# gate_driver2.net
KiCad netlist of a schematic drawn in EAGLE
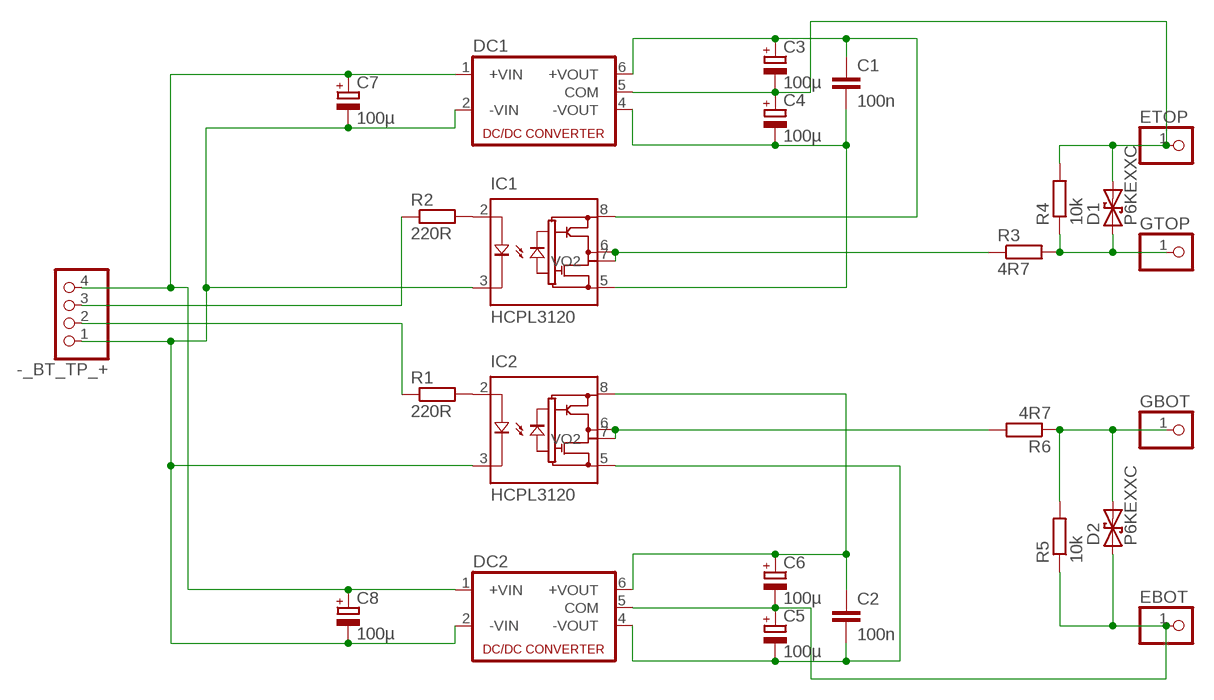
[diagram p0: schematic, sheet 1]

(export (version "E")
  (design (tool "Eeschema 10.0.6"))
  (components
    (comp (ref "-_BT_TP_+")
      (value "PINHD-1X4")
      (footprint "eagle-import:1X04")
      (libsource (lib "eagle-import") (part "PINHD-1X4"))
    )
    (comp (ref "C1")
      (value "100n")
      (footprint "eagle-import:C050-025X075")
      (libsource (lib "eagle-import") (part "C-EU050-025X075"))
    )
    (comp (ref "C2")
      (value "100n")
      (footprint "eagle-import:C050-025X075")
      (libsource (lib "eagle-import") (part "C-EU050-025X075"))
    )
    (comp (ref "C3")
      (value "100µ")
      (footprint "eagle-import:E2,5-6E")
      (libsource (lib "eagle-import") (part "CPOL-EUE2,5-6E"))
    )
    (comp (ref "C4")
      (value "100µ")
      (footprint "eagle-import:E2,5-6E")
      (libsource (lib "eagle-import") (part "CPOL-EUE2,5-6E"))
    )
    (comp (ref "C5")
      (value "100µ")
      (footprint "eagle-import:E2,5-6E")
      (libsource (lib "eagle-import") (part "CPOL-EUE2,5-6E"))
    )
    (comp (ref "C6")
      (value "100µ")
      (footprint "eagle-import:E2,5-6E")
      (libsource (lib "eagle-import") (part "CPOL-EUE2,5-6E"))
    )
    (comp (ref "C7")
      (value "100µ")
      (footprint "eagle-import:E2,5-5")
      (libsource (lib "eagle-import") (part "CPOL-EUE2.5-5"))
    )
    (comp (ref "C8")
      (value "100µ")
      (footprint "eagle-import:E2,5-5")
      (libsource (lib "eagle-import") (part "CPOL-EUE2.5-5"))
    )
    (comp (ref "D1")
      (value "P6KEXXC")
      (footprint "eagle-import:CB417-15")
      (libsource (lib "eagle-import") (part "P6KEXXC"))
    )
    (comp (ref "D2")
      (value "P6KEXXC")
      (footprint "eagle-import:CB417-15")
      (libsource (lib "eagle-import") (part "P6KEXXC"))
    )
    (comp (ref "DC1")
      (value "NMA")
      (footprint "eagle-import:NMA")
      (libsource (lib "eagle-import") (part "NMA"))
    )
    (comp (ref "DC2")
      (value "NMA")
      (footprint "eagle-import:NMA")
      (libsource (lib "eagle-import") (part "NMA"))
    )
    (comp (ref "EBOT")
      (value "PINHD-1X1")
      (footprint "eagle-import:1X01")
      (libsource (lib "eagle-import") (part "PINHD-1X1"))
    )
    (comp (ref "ETOP")
      (value "PINHD-1X1")
      (footprint "eagle-import:1X01")
      (libsource (lib "eagle-import") (part "PINHD-1X1"))
    )
    (comp (ref "GBOT")
      (value "PINHD-1X1")
      (footprint "eagle-import:1X01")
      (libsource (lib "eagle-import") (part "PINHD-1X1"))
    )
    (comp (ref "GTOP")
      (value "PINHD-1X1")
      (footprint "eagle-import:1X01")
      (libsource (lib "eagle-import") (part "PINHD-1X1"))
    )
    (comp (ref "IC1")
      (value "HCPL3120")
      (footprint "eagle-import:DIL08")
      (libsource (lib "eagle-import") (part "HCPL3120"))
    )
    (comp (ref "IC2")
      (value "HCPL3120")
      (footprint "eagle-import:DIL08")
      (libsource (lib "eagle-import") (part "HCPL3120"))
    )
    (comp (ref "R1")
      (value "220R")
      (footprint "eagle-import:0207_10")
      (libsource (lib "eagle-import") (part "R-EU_0207/10"))
    )
    (comp (ref "R2")
      (value "220R")
      (footprint "eagle-import:0207_10")
      (libsource (lib "eagle-import") (part "R-EU_0207/10"))
    )
    (comp (ref "R3")
      (value "4R7")
      (footprint "eagle-import:0309_12")
      (libsource (lib "eagle-import") (part "R-EU_0309/12"))
    )
    (comp (ref "R4")
      (value "10k")
      (footprint "eagle-import:0207_10")
      (libsource (lib "eagle-import") (part "R-EU_0207/10"))
    )
    (comp (ref "R5")
      (value "10k")
      (footprint "eagle-import:0207_10")
      (libsource (lib "eagle-import") (part "R-EU_0207/10"))
    )
    (comp (ref "R6")
      (value "4R7")
      (footprint "eagle-import:0309_12")
      (libsource (lib "eagle-import") (part "R-EU_0309/12"))
    )
  )
  (nets
    (net (code "1") (name "Net-(-_BT_TP_+-Pad2)") (class "Default")
      (node (ref "-_BT_TP_+") (pin "2") (pinfunction "2_2") (pintype "passive"))
      (node (ref "R1") (pin "1") (pinfunction "1_1") (pintype "passive"))
    )
    (net (code "2") (name "Net-(-_BT_TP_+-Pad3)") (class "Default")
      (node (ref "-_BT_TP_+") (pin "3") (pinfunction "3_3") (pintype "passive"))
      (node (ref "R2") (pin "1") (pinfunction "1_1") (pintype "passive"))
    )
    (net (code "3") (name "Net-(D1-1)") (class "Default")
      (node (ref "D1") (pin "A") (pinfunction "1_A") (pintype "passive"))
      (node (ref "GTOP") (pin "1") (pinfunction "1_1") (pintype "passive"))
      (node (ref "R3") (pin "2") (pinfunction "2_2") (pintype "passive"))
      (node (ref "R4") (pin "1") (pinfunction "1_1") (pintype "passive"))
    )
    (net (code "4") (name "Net-(D1-2)") (class "Default")
      (node (ref "C3") (pin "-") (pinfunction "-_-") (pintype "passive"))
      (node (ref "C4") (pin "+") (pinfunction "+_+") (pintype "passive"))
      (node (ref "D1") (pin "C") (pinfunction "2_C") (pintype "passive"))
      (node (ref "DC1") (pin "5") (pinfunction "COM_5") (pintype "passive"))
      (node (ref "ETOP") (pin "1") (pinfunction "1_1") (pintype "passive"))
      (node (ref "R4") (pin "2") (pinfunction "2_2") (pintype "passive"))
    )
    (net (code "5") (name "Net-(D2-1)") (class "Default")
      (node (ref "C5") (pin "+") (pinfunction "+_+") (pintype "passive"))
      (node (ref "C6") (pin "-") (pinfunction "-_-") (pintype "passive"))
      (node (ref "D2") (pin "A") (pinfunction "1_A") (pintype "passive"))
      (node (ref "DC2") (pin "5") (pinfunction "COM_5") (pintype "passive"))
      (node (ref "EBOT") (pin "1") (pinfunction "1_1") (pintype "passive"))
      (node (ref "R5") (pin "1") (pinfunction "1_1") (pintype "passive"))
    )
    (net (code "6") (name "Net-(D2-2)") (class "Default")
      (node (ref "D2") (pin "C") (pinfunction "2_C") (pintype "passive"))
      (node (ref "GBOT") (pin "1") (pinfunction "1_1") (pintype "passive"))
      (node (ref "R5") (pin "2") (pinfunction "2_2") (pintype "passive"))
      (node (ref "R6") (pin "1") (pinfunction "1_1") (pintype "passive"))
    )
    (net (code "7") (name "Net-(DC1-+VIN)") (class "Default")
      (node (ref "-_BT_TP_+") (pin "4") (pinfunction "4_4") (pintype "passive"))
      (node (ref "C7") (pin "+") (pinfunction "+_+") (pintype "passive"))
      (node (ref "C8") (pin "+") (pinfunction "+_+") (pintype "passive"))
      (node (ref "DC1") (pin "1") (pinfunction "+VIN_1") (pintype "passive"))
      (node (ref "DC2") (pin "1") (pinfunction "+VIN_1") (pintype "passive"))
    )
    (net (code "8") (name "Net-(DC1-+VOUT)") (class "Default")
      (node (ref "C1") (pin "1") (pinfunction "1_1") (pintype "passive"))
      (node (ref "C3") (pin "+") (pinfunction "+_+") (pintype "passive"))
      (node (ref "DC1") (pin "6") (pinfunction "+VOUT_6") (pintype "passive"))
      (node (ref "IC1") (pin "8") (pinfunction "VCC_8") (pintype "passive"))
    )
    (net (code "9") (name "Net-(DC1--VIN)") (class "Default")
      (node (ref "-_BT_TP_+") (pin "1") (pinfunction "1_1") (pintype "passive"))
      (node (ref "C7") (pin "-") (pinfunction "-_-") (pintype "passive"))
      (node (ref "C8") (pin "-") (pinfunction "-_-") (pintype "passive"))
      (node (ref "DC1") (pin "2") (pinfunction "-VIN_2") (pintype "passive"))
      (node (ref "DC2") (pin "2") (pinfunction "-VIN_2") (pintype "passive"))
      (node (ref "IC1") (pin "3") (pinfunction "CATHODE_3") (pintype "passive"))
      (node (ref "IC2") (pin "3") (pinfunction "CATHODE_3") (pintype "passive"))
    )
    (net (code "10") (name "Net-(DC1--VOUT)") (class "Default")
      (node (ref "C1") (pin "2") (pinfunction "2_2") (pintype "passive"))
      (node (ref "C4") (pin "-") (pinfunction "-_-") (pintype "passive"))
      (node (ref "DC1") (pin "4") (pinfunction "-VOUT_4") (pintype "passive"))
      (node (ref "IC1") (pin "5") (pinfunction "VEE_5") (pintype "passive"))
    )
    (net (code "11") (name "Net-(DC2-+VOUT)") (class "Default")
      (node (ref "C2") (pin "1") (pinfunction "1_1") (pintype "passive"))
      (node (ref "C6") (pin "+") (pinfunction "+_+") (pintype "passive"))
      (node (ref "DC2") (pin "6") (pinfunction "+VOUT_6") (pintype "passive"))
      (node (ref "IC2") (pin "8") (pinfunction "VCC_8") (pintype "passive"))
    )
    (net (code "12") (name "Net-(DC2--VOUT)") (class "Default")
      (node (ref "C2") (pin "2") (pinfunction "2_2") (pintype "passive"))
      (node (ref "C5") (pin "-") (pinfunction "-_-") (pintype "passive"))
      (node (ref "DC2") (pin "4") (pinfunction "-VOUT_4") (pintype "passive"))
      (node (ref "IC2") (pin "5") (pinfunction "VEE_5") (pintype "passive"))
    )
    (net (code "13") (name "Net-(IC1-ANODE)") (class "Default")
      (node (ref "IC1") (pin "2") (pinfunction "ANODE_2") (pintype "passive"))
      (node (ref "R2") (pin "2") (pinfunction "2_2") (pintype "passive"))
    )
    (net (code "14") (name "Net-(IC1-VO)") (class "Default")
      (node (ref "IC1") (pin "6") (pinfunction "VO_6") (pintype "passive"))
      (node (ref "IC1") (pin "7") (pinfunction "VO2_7") (pintype "bidirectional"))
      (node (ref "R3") (pin "1") (pinfunction "1_1") (pintype "passive"))
    )
    (net (code "15") (name "Net-(IC2-ANODE)") (class "Default")
      (node (ref "IC2") (pin "2") (pinfunction "ANODE_2") (pintype "passive"))
      (node (ref "R1") (pin "2") (pinfunction "2_2") (pintype "passive"))
    )
    (net (code "16") (name "Net-(IC2-VO)") (class "Default")
      (node (ref "IC2") (pin "6") (pinfunction "VO_6") (pintype "passive"))
      (node (ref "IC2") (pin "7") (pinfunction "VO2_7") (pintype "bidirectional"))
      (node (ref "R6") (pin "2") (pinfunction "2_2") (pintype "passive"))
    )
  )
)
